# M3-Module1.net
KiCad netlist of a schematic drawn in EAGLE
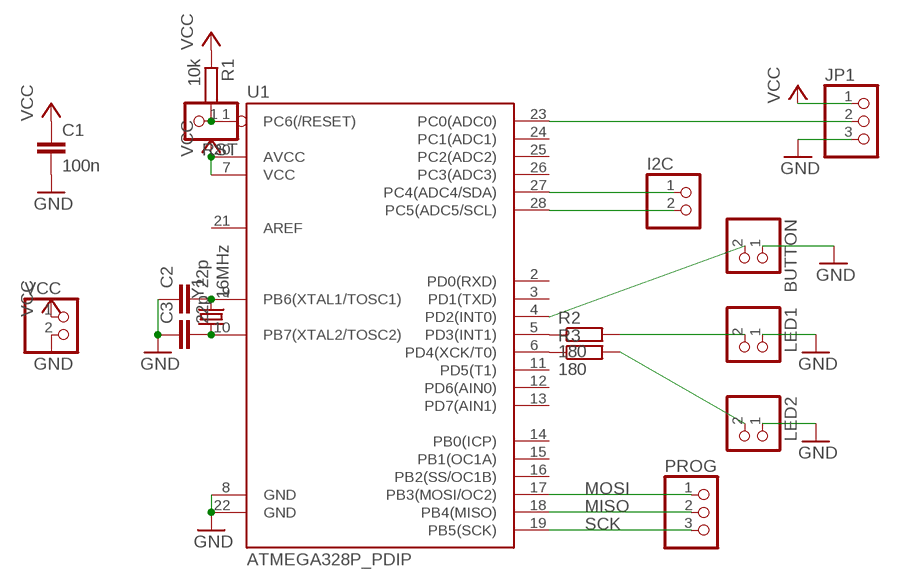
[diagram p0: schematic, sheet 1]

(export (version "E")
  (design (tool "Eeschema 10.0.6"))
  (components
    (comp (ref "BUTTON")
      (value "PINHD-1X2")
      (footprint "eagle-import:1X02")
      (libsource (lib "eagle-import") (part "PINHD-1X2"))
    )
    (comp (ref "C1")
      (value "100n")
      (footprint "eagle-import:C025-025X050")
      (libsource (lib "eagle-import") (part "C-EU025-025X050"))
    )
    (comp (ref "C2")
      (value "22p")
      (footprint "eagle-import:C025-025X050")
      (libsource (lib "eagle-import") (part "C-EU025-025X050"))
    )
    (comp (ref "C3")
      (value "22p")
      (footprint "eagle-import:C025-025X050")
      (libsource (lib "eagle-import") (part "C-EU025-025X050"))
    )
    (comp (ref "I2C")
      (value "PINHD-1X2")
      (footprint "eagle-import:1X02")
      (libsource (lib "eagle-import") (part "PINHD-1X2"))
    )
    (comp (ref "JP1")
      (value "PINHD-1X3")
      (footprint "eagle-import:1X03")
      (libsource (lib "eagle-import") (part "PINHD-1X3"))
    )
    (comp (ref "LED1")
      (value "PINHD-1X2")
      (footprint "eagle-import:1X02")
      (libsource (lib "eagle-import") (part "PINHD-1X2"))
    )
    (comp (ref "LED2")
      (value "PINHD-1X2")
      (footprint "eagle-import:1X02")
      (libsource (lib "eagle-import") (part "PINHD-1X2"))
    )
    (comp (ref "PROG")
      (value "PINHD-1X3")
      (footprint "eagle-import:1X03")
      (libsource (lib "eagle-import") (part "PINHD-1X3"))
    )
    (comp (ref "R1")
      (value "10k")
      (footprint "eagle-import:0204_5")
      (libsource (lib "eagle-import") (part "R-EU_0204/5"))
    )
    (comp (ref "R2")
      (value "180")
      (footprint "eagle-import:0204_5")
      (libsource (lib "eagle-import") (part "R-EU_0204/5"))
    )
    (comp (ref "R3")
      (value "180")
      (footprint "eagle-import:0204_5")
      (libsource (lib "eagle-import") (part "R-EU_0204/5"))
    )
    (comp (ref "RST")
      (value "PINHD-1X1")
      (footprint "eagle-import:1X01")
      (libsource (lib "eagle-import") (part "PINHD-1X1"))
    )
    (comp (ref "U1")
      (value "ATMEGA328P_PDIP")
      (footprint "eagle-import:DIL28-3")
      (libsource (lib "eagle-import") (part "ATMEGA328P_PDIP"))
    )
    (comp (ref "VCC")
      (value "PINHD-1X2")
      (footprint "eagle-import:1X02")
      (libsource (lib "eagle-import") (part "PINHD-1X2"))
    )
    (comp (ref "Y1")
      (value "16MHz")
      (footprint "eagle-import:HC49US")
      (libsource (lib "eagle-import") (part "CRYSTALHC49US"))
    )
  )
  (nets
    (net (code "1") (name "/MISO") (class "Default")
      (node (ref "PROG") (pin "2") (pinfunction "2_2") (pintype "passive"))
      (node (ref "U1") (pin "18") (pinfunction "PB4(MISO)_18") (pintype "bidirectional"))
    )
    (net (code "2") (name "/MOSI") (class "Default")
      (node (ref "PROG") (pin "1") (pinfunction "1_1") (pintype "passive"))
      (node (ref "U1") (pin "17") (pinfunction "PB3(MOSI/OC2)_17") (pintype "bidirectional"))
    )
    (net (code "3") (name "/SCK") (class "Default")
      (node (ref "PROG") (pin "3") (pinfunction "3_3") (pintype "passive"))
      (node (ref "U1") (pin "19") (pinfunction "PB5(SCK)_19") (pintype "bidirectional"))
    )
    (net (code "4") (name "GND") (class "Default")
      (node (ref "BUTTON") (pin "1") (pinfunction "1_1") (pintype "passive"))
      (node (ref "C1") (pin "2") (pinfunction "2_2") (pintype "passive"))
      (node (ref "C2") (pin "1") (pinfunction "1_1") (pintype "passive"))
      (node (ref "C3") (pin "1") (pinfunction "1_1") (pintype "passive"))
      (node (ref "JP1") (pin "3") (pinfunction "3_3") (pintype "passive"))
      (node (ref "LED1") (pin "1") (pinfunction "1_1") (pintype "passive"))
      (node (ref "LED2") (pin "1") (pinfunction "1_1") (pintype "passive"))
      (node (ref "U1") (pin "22") (pinfunction "GND_22") (pintype "bidirectional"))
      (node (ref "U1") (pin "8") (pinfunction "GND_8") (pintype "bidirectional"))
      (node (ref "VCC") (pin "2") (pinfunction "2_2") (pintype "passive"))
    )
    (net (code "5") (name "Net-(LED1-Pad2)") (class "Default")
      (node (ref "LED1") (pin "2") (pinfunction "2_2") (pintype "passive"))
      (node (ref "R2") (pin "2") (pinfunction "2_2") (pintype "passive"))
    )
    (net (code "6") (name "Net-(LED2-Pad2)") (class "Default")
      (node (ref "LED2") (pin "2") (pinfunction "2_2") (pintype "passive"))
      (node (ref "R3") (pin "2") (pinfunction "2_2") (pintype "passive"))
    )
    (net (code "7") (name "Net-(U1-PB6(XTAL1{slash}TOSC1))") (class "Default")
      (node (ref "C2") (pin "2") (pinfunction "2_2") (pintype "passive"))
      (node (ref "U1") (pin "9") (pinfunction "PB6(XTAL1/TOSC1)_9") (pintype "bidirectional"))
      (node (ref "Y1") (pin "2") (pinfunction "2_2") (pintype "passive"))
    )
    (net (code "8") (name "Net-(U1-PB7(XTAL2{slash}TOSC2))") (class "Default")
      (node (ref "C3") (pin "2") (pinfunction "2_2") (pintype "passive"))
      (node (ref "U1") (pin "10") (pinfunction "PB7(XTAL2/TOSC2)_10") (pintype "bidirectional"))
      (node (ref "Y1") (pin "1") (pinfunction "1_1") (pintype "passive"))
    )
    (net (code "9") (name "Net-(U1-PC0(ADC0))") (class "Default")
      (node (ref "JP1") (pin "2") (pinfunction "2_2") (pintype "passive"))
      (node (ref "U1") (pin "23") (pinfunction "PC0(ADC0)_23") (pintype "bidirectional"))
    )
    (net (code "10") (name "Net-(U1-PC4(ADC4{slash}SDA))") (class "Default")
      (node (ref "I2C") (pin "1") (pinfunction "1_1") (pintype "passive"))
      (node (ref "U1") (pin "27") (pinfunction "PC4(ADC4/SDA)_27") (pintype "bidirectional"))
    )
    (net (code "11") (name "Net-(U1-PC5(ADC5{slash}SCL))") (class "Default")
      (node (ref "I2C") (pin "2") (pinfunction "2_2") (pintype "passive"))
      (node (ref "U1") (pin "28") (pinfunction "PC5(ADC5/SCL)_28") (pintype "bidirectional"))
    )
    (net (code "12") (name "Net-(U1-PC6({slash}RESET))") (class "Default")
      (node (ref "R1") (pin "2") (pinfunction "2_2") (pintype "passive"))
      (node (ref "RST") (pin "1") (pinfunction "1_1") (pintype "passive"))
      (node (ref "U1") (pin "1") (pinfunction "PC6(/RESET)_1") (pintype "bidirectional"))
    )
    (net (code "13") (name "Net-(U1-PD2(INT0))") (class "Default")
      (node (ref "BUTTON") (pin "2") (pinfunction "2_2") (pintype "passive"))
      (node (ref "U1") (pin "4") (pinfunction "PD2(INT0)_4") (pintype "bidirectional"))
    )
    (net (code "14") (name "Net-(U1-PD3(INT1))") (class "Default")
      (node (ref "R2") (pin "1") (pinfunction "1_1") (pintype "passive"))
      (node (ref "U1") (pin "5") (pinfunction "PD3(INT1)_5") (pintype "bidirectional"))
    )
    (net (code "15") (name "Net-(U1-PD4(XCK{slash}T0))") (class "Default")
      (node (ref "R3") (pin "1") (pinfunction "1_1") (pintype "passive"))
      (node (ref "U1") (pin "6") (pinfunction "PD4(XCK/T0)_6") (pintype "bidirectional"))
    )
    (net (code "16") (name "VCC") (class "Default")
      (node (ref "C1") (pin "1") (pinfunction "1_1") (pintype "passive"))
      (node (ref "JP1") (pin "1") (pinfunction "1_1") (pintype "passive"))
      (node (ref "R1") (pin "1") (pinfunction "1_1") (pintype "passive"))
      (node (ref "U1") (pin "20") (pinfunction "AVCC_20") (pintype "bidirectional"))
      (node (ref "U1") (pin "7") (pinfunction "VCC_7") (pintype "bidirectional"))
      (node (ref "VCC") (pin "1") (pinfunction "1_1") (pintype "passive"))
    )
    (net (code "17") (name "unconnected-(U1-AREF-Pad21)") (class "Default")
      (node (ref "U1") (pin "21") (pinfunction "AREF_21") (pintype "bidirectional"))
    )
    (net (code "18") (name "unconnected-(U1-PB0(ICP)-Pad14)") (class "Default")
      (node (ref "U1") (pin "14") (pinfunction "PB0(ICP)_14") (pintype "bidirectional"))
    )
    (net (code "19") (name "unconnected-(U1-PB1(OC1A)-Pad15)") (class "Default")
      (node (ref "U1") (pin "15") (pinfunction "PB1(OC1A)_15") (pintype "bidirectional"))
    )
    (net (code "20") (name "unconnected-(U1-PB2(SS{slash}OC1B)-Pad16)") (class "Default")
      (node (ref "U1") (pin "16") (pinfunction "PB2(SS/OC1B)_16") (pintype "bidirectional"))
    )
    (net (code "21") (name "unconnected-(U1-PC1(ADC1)-Pad24)") (class "Default")
      (node (ref "U1") (pin "24") (pinfunction "PC1(ADC1)_24") (pintype "bidirectional"))
    )
    (net (code "22") (name "unconnected-(U1-PC2(ADC2)-Pad25)") (class "Default")
      (node (ref "U1") (pin "25") (pinfunction "PC2(ADC2)_25") (pintype "bidirectional"))
    )
    (net (code "23") (name "unconnected-(U1-PC3(ADC3)-Pad26)") (class "Default")
      (node (ref "U1") (pin "26") (pinfunction "PC3(ADC3)_26") (pintype "bidirectional"))
    )
    (net (code "24") (name "unconnected-(U1-PD0(RXD)-Pad2)") (class "Default")
      (node (ref "U1") (pin "2") (pinfunction "PD0(RXD)_2") (pintype "bidirectional"))
    )
    (net (code "25") (name "unconnected-(U1-PD1(TXD)-Pad3)") (class "Default")
      (node (ref "U1") (pin "3") (pinfunction "PD1(TXD)_3") (pintype "bidirectional"))
    )
    (net (code "26") (name "unconnected-(U1-PD5(T1)-Pad11)") (class "Default")
      (node (ref "U1") (pin "11") (pinfunction "PD5(T1)_11") (pintype "bidirectional"))
    )
    (net (code "27") (name "unconnected-(U1-PD6(AIN0)-Pad12)") (class "Default")
      (node (ref "U1") (pin "12") (pinfunction "PD6(AIN0)_12") (pintype "bidirectional"))
    )
    (net (code "28") (name "unconnected-(U1-PD7(AIN1)-Pad13)") (class "Default")
      (node (ref "U1") (pin "13") (pinfunction "PD7(AIN1)_13") (pintype "bidirectional"))
    )
  )
)
